# 08_-_Solar.net
KiCad netlist of a schematic drawn in Altium Designer
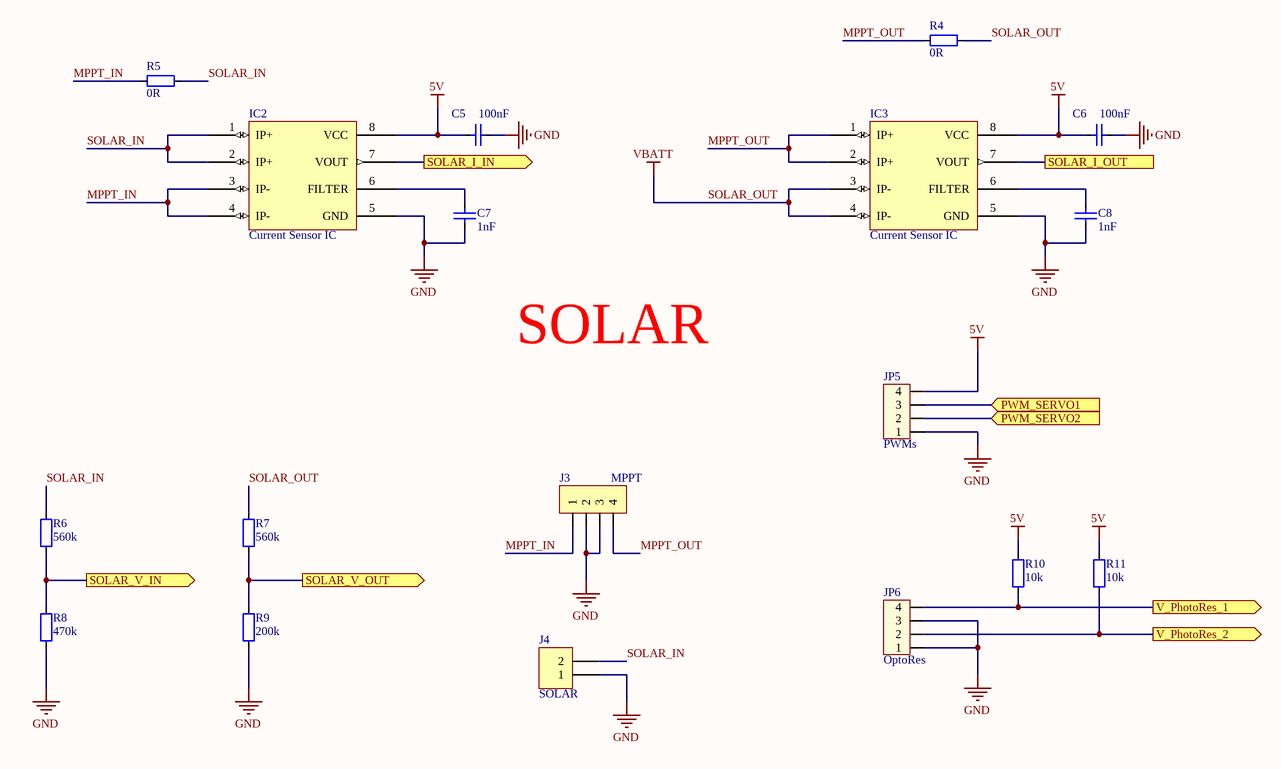
[diagram p0: [08] - Solar.SchDoc]

(export (version "E")
  (design (tool "Eeschema 10.0.6"))
  (components
    (comp (ref "C5")
      (value "100nF")
      (footprint "CAP_0805")
      (description "Capacitor")
      (fields (field (name "PUBLISHER") "Altium Limited"))
      (libsource (lib "My Library") (part "CapSMD"))
    )
    (comp (ref "C6")
      (value "100nF")
      (footprint "CAP_0805")
      (description "Capacitor")
      (fields (field (name "PUBLISHER") "Altium Limited"))
      (libsource (lib "My Library") (part "CapSMD"))
    )
    (comp (ref "C7")
      (value "1nF")
      (footprint "CAP_0805")
      (description "Capacitor")
      (fields (field (name "PUBLISHER") "Altium Limited"))
      (libsource (lib "My Library") (part "CapSMD"))
    )
    (comp (ref "C8")
      (value "1nF")
      (footprint "CAP_0805")
      (description "Capacitor")
      (fields (field (name "PUBLISHER") "Altium Limited"))
      (libsource (lib "My Library") (part "CapSMD"))
    )
    (comp (ref "IC2")
      (value "Current Sensor IC")
      (footprint "SOIC-8")
      (libsource (lib "My Library") (part "ACS712"))
    )
    (comp (ref "IC3")
      (value "Current Sensor IC")
      (footprint "SOIC-8")
      (libsource (lib "My Library") (part "ACS712"))
    )
    (comp (ref "J3")
      (value "MPPT")
      (footprint "JP4-C1T")
      (description "WR-PHD 2.54 mm Angled Socket Header")
      (fields
        (field (name "MANUFACTURER") "Würth Elektronik eiSos GmbH")
        (field (name "PARTNO") "613004143121")
        (field (name "CREATED BY") "Karrer Zheng")
      )
      (libsource (lib "My Library") (part "JP4"))
    )
    (comp (ref "J4")
      (value "SOLAR")
      (footprint "KF2-5.08")
      (fields
        (field (name "MANUFACTURER") "Würth Elektronik eiSos GmbH")
        (field (name "PARTNO") "691103110002")
        (field (name "CREATED BY") "Karrer Zheng")
      )
      (libsource (lib "My Library") (part "KF2"))
    )
    (comp (ref "JP5")
      (value "PWMs")
      (footprint "CON4")
      (description "Connector 4")
      (libsource (lib "My Library") (part "Con4"))
    )
    (comp (ref "JP6")
      (value "OptoRes")
      (footprint "CON4")
      (description "Connector 4")
      (libsource (lib "My Library") (part "Con4"))
    )
    (comp (ref "R4")
      (value "0R")
      (footprint "RES-SMD-0805")
      (description "Resistor")
      (fields
        (field (name "MANUFACTURER") "Generic Components")
        (field (name "PUBLISHER") "Altium Hobart Technology Centre")
      )
      (libsource (lib "My Library") (part "Resistor - SMD"))
    )
    (comp (ref "R5")
      (value "0R")
      (footprint "RES-SMD-0805")
      (description "Resistor")
      (fields
        (field (name "MANUFACTURER") "Generic Components")
        (field (name "PUBLISHER") "Altium Hobart Technology Centre")
      )
      (libsource (lib "My Library") (part "Resistor - SMD"))
    )
    (comp (ref "R6")
      (value "560k")
      (footprint "RES-SMD-0805")
      (description "Resistor")
      (fields
        (field (name "MANUFACTURER") "Generic Components")
        (field (name "PUBLISHER") "Altium Hobart Technology Centre")
      )
      (libsource (lib "My Library") (part "Resistor - SMD"))
    )
    (comp (ref "R7")
      (value "560k")
      (footprint "RES-SMD-0805")
      (description "Resistor")
      (fields
        (field (name "MANUFACTURER") "Generic Components")
        (field (name "PUBLISHER") "Altium Hobart Technology Centre")
      )
      (libsource (lib "My Library") (part "Resistor - SMD"))
    )
    (comp (ref "R8")
      (value "470k")
      (footprint "RES-SMD-0805")
      (description "Resistor")
      (fields
        (field (name "MANUFACTURER") "Generic Components")
        (field (name "PUBLISHER") "Altium Hobart Technology Centre")
      )
      (libsource (lib "My Library") (part "Resistor - SMD"))
    )
    (comp (ref "R9")
      (value "200k")
      (footprint "RES-SMD-0805")
      (description "Resistor")
      (fields
        (field (name "MANUFACTURER") "Generic Components")
        (field (name "PUBLISHER") "Altium Hobart Technology Centre")
      )
      (libsource (lib "My Library") (part "Resistor - SMD"))
    )
    (comp (ref "R10")
      (value "10k")
      (footprint "RES-SMD-0805")
      (description "Resistor")
      (fields
        (field (name "MANUFACTURER") "Generic Components")
        (field (name "PUBLISHER") "Altium Hobart Technology Centre")
      )
      (libsource (lib "My Library") (part "Resistor - SMD"))
    )
    (comp (ref "R11")
      (value "10k")
      (footprint "RES-SMD-0805")
      (description "Resistor")
      (fields
        (field (name "MANUFACTURER") "Generic Components")
        (field (name "PUBLISHER") "Altium Hobart Technology Centre")
      )
      (libsource (lib "My Library") (part "Resistor - SMD"))
    )
  )
  (nets
    (net (code "1") (name "/MPPT_IN") (class "Default")
      (node (ref "IC2") (pin "3") (pinfunction "IP-_3") (pintype "bidirectional"))
      (node (ref "IC2") (pin "4") (pinfunction "IP-_4") (pintype "bidirectional"))
      (node (ref "J3") (pin "1") (pinfunction "1_1") (pintype "passive"))
      (node (ref "R5") (pin "2") (pinfunction "2_2") (pintype "passive"))
    )
    (net (code "2") (name "/MPPT_OUT") (class "Default")
      (node (ref "IC3") (pin "1") (pinfunction "IP+_1") (pintype "bidirectional"))
      (node (ref "IC3") (pin "2") (pinfunction "IP+_2") (pintype "bidirectional"))
      (node (ref "J3") (pin "4") (pinfunction "4_4") (pintype "passive"))
      (node (ref "R4") (pin "2") (pinfunction "2_2") (pintype "passive"))
    )
    (net (code "3") (name "/PWM_SERVO1") (class "Default")
      (node (ref "JP5") (pin "3") (pinfunction "3_3") (pintype "passive"))
    )
    (net (code "4") (name "/PWM_SERVO2") (class "Default")
      (node (ref "JP5") (pin "2") (pinfunction "2_2") (pintype "passive"))
    )
    (net (code "5") (name "/SOLAR_IN") (class "Default")
      (node (ref "IC2") (pin "1") (pinfunction "IP+_1") (pintype "bidirectional"))
      (node (ref "IC2") (pin "2") (pinfunction "IP+_2") (pintype "bidirectional"))
      (node (ref "J4") (pin "2") (pinfunction "2_2") (pintype "passive"))
      (node (ref "R5") (pin "1") (pinfunction "1_1") (pintype "passive"))
      (node (ref "R6") (pin "2") (pinfunction "2_2") (pintype "passive"))
    )
    (net (code "6") (name "/SOLAR_I_IN") (class "Default")
      (node (ref "IC2") (pin "7") (pinfunction "VOUT_7") (pintype "output"))
    )
    (net (code "7") (name "/SOLAR_I_OUT") (class "Default")
      (node (ref "IC3") (pin "7") (pinfunction "VOUT_7") (pintype "output"))
    )
    (net (code "8") (name "/SOLAR_V_IN") (class "Default")
      (node (ref "R6") (pin "1") (pinfunction "1_1") (pintype "passive"))
      (node (ref "R8") (pin "2") (pinfunction "2_2") (pintype "passive"))
    )
    (net (code "9") (name "/SOLAR_V_OUT") (class "Default")
      (node (ref "R7") (pin "1") (pinfunction "1_1") (pintype "passive"))
      (node (ref "R9") (pin "2") (pinfunction "2_2") (pintype "passive"))
    )
    (net (code "10") (name "/V_PhotoRes_1") (class "Default")
      (node (ref "JP6") (pin "4") (pinfunction "4_4") (pintype "passive"))
      (node (ref "R10") (pin "1") (pinfunction "1_1") (pintype "passive"))
    )
    (net (code "11") (name "/V_PhotoRes_2") (class "Default")
      (node (ref "JP6") (pin "2") (pinfunction "2_2") (pintype "passive"))
      (node (ref "R11") (pin "1") (pinfunction "1_1") (pintype "passive"))
    )
    (net (code "12") (name "5V") (class "Default")
      (node (ref "C5") (pin "2") (pinfunction "2_2") (pintype "passive"))
      (node (ref "C6") (pin "2") (pinfunction "2_2") (pintype "passive"))
      (node (ref "IC2") (pin "8") (pinfunction "VCC_8") (pintype "passive"))
      (node (ref "IC3") (pin "8") (pinfunction "VCC_8") (pintype "passive"))
      (node (ref "JP5") (pin "4") (pinfunction "4_4") (pintype "passive"))
      (node (ref "R10") (pin "2") (pinfunction "2_2") (pintype "passive"))
      (node (ref "R11") (pin "2") (pinfunction "2_2") (pintype "passive"))
    )
    (net (code "13") (name "GND") (class "Default")
      (node (ref "C5") (pin "1") (pinfunction "1_1") (pintype "passive"))
      (node (ref "C6") (pin "1") (pinfunction "1_1") (pintype "passive"))
      (node (ref "C7") (pin "1") (pinfunction "1_1") (pintype "passive"))
      (node (ref "C8") (pin "1") (pinfunction "1_1") (pintype "passive"))
      (node (ref "IC2") (pin "5") (pinfunction "GND_5") (pintype "passive"))
      (node (ref "IC3") (pin "5") (pinfunction "GND_5") (pintype "passive"))
      (node (ref "J3") (pin "2") (pinfunction "2_2") (pintype "passive"))
      (node (ref "J3") (pin "3") (pinfunction "3_3") (pintype "passive"))
      (node (ref "J4") (pin "1") (pinfunction "1_1") (pintype "passive"))
      (node (ref "JP5") (pin "1") (pinfunction "1_1") (pintype "passive"))
      (node (ref "JP6") (pin "1") (pinfunction "1_1") (pintype "passive"))
      (node (ref "JP6") (pin "3") (pinfunction "3_3") (pintype "passive"))
      (node (ref "R8") (pin "1") (pinfunction "1_1") (pintype "passive"))
      (node (ref "R9") (pin "1") (pinfunction "1_1") (pintype "passive"))
    )
    (net (code "14") (name "Net-(IC2-FILTER)") (class "Default")
      (node (ref "C7") (pin "2") (pinfunction "2_2") (pintype "passive"))
      (node (ref "IC2") (pin "6") (pinfunction "FILTER_6") (pintype "passive"))
    )
    (net (code "15") (name "Net-(IC3-FILTER)") (class "Default")
      (node (ref "C8") (pin "2") (pinfunction "2_2") (pintype "passive"))
      (node (ref "IC3") (pin "6") (pinfunction "FILTER_6") (pintype "passive"))
    )
    (net (code "16") (name "VBATT") (class "Default")
      (node (ref "IC3") (pin "3") (pinfunction "IP-_3") (pintype "bidirectional"))
      (node (ref "IC3") (pin "4") (pinfunction "IP-_4") (pintype "bidirectional"))
      (node (ref "R4") (pin "1") (pinfunction "1_1") (pintype "passive"))
      (node (ref "R7") (pin "2") (pinfunction "2_2") (pintype "passive"))
    )
  )
)
